# Air_Purification_System.net
KiCad netlist of a schematic drawn in Altium Designer
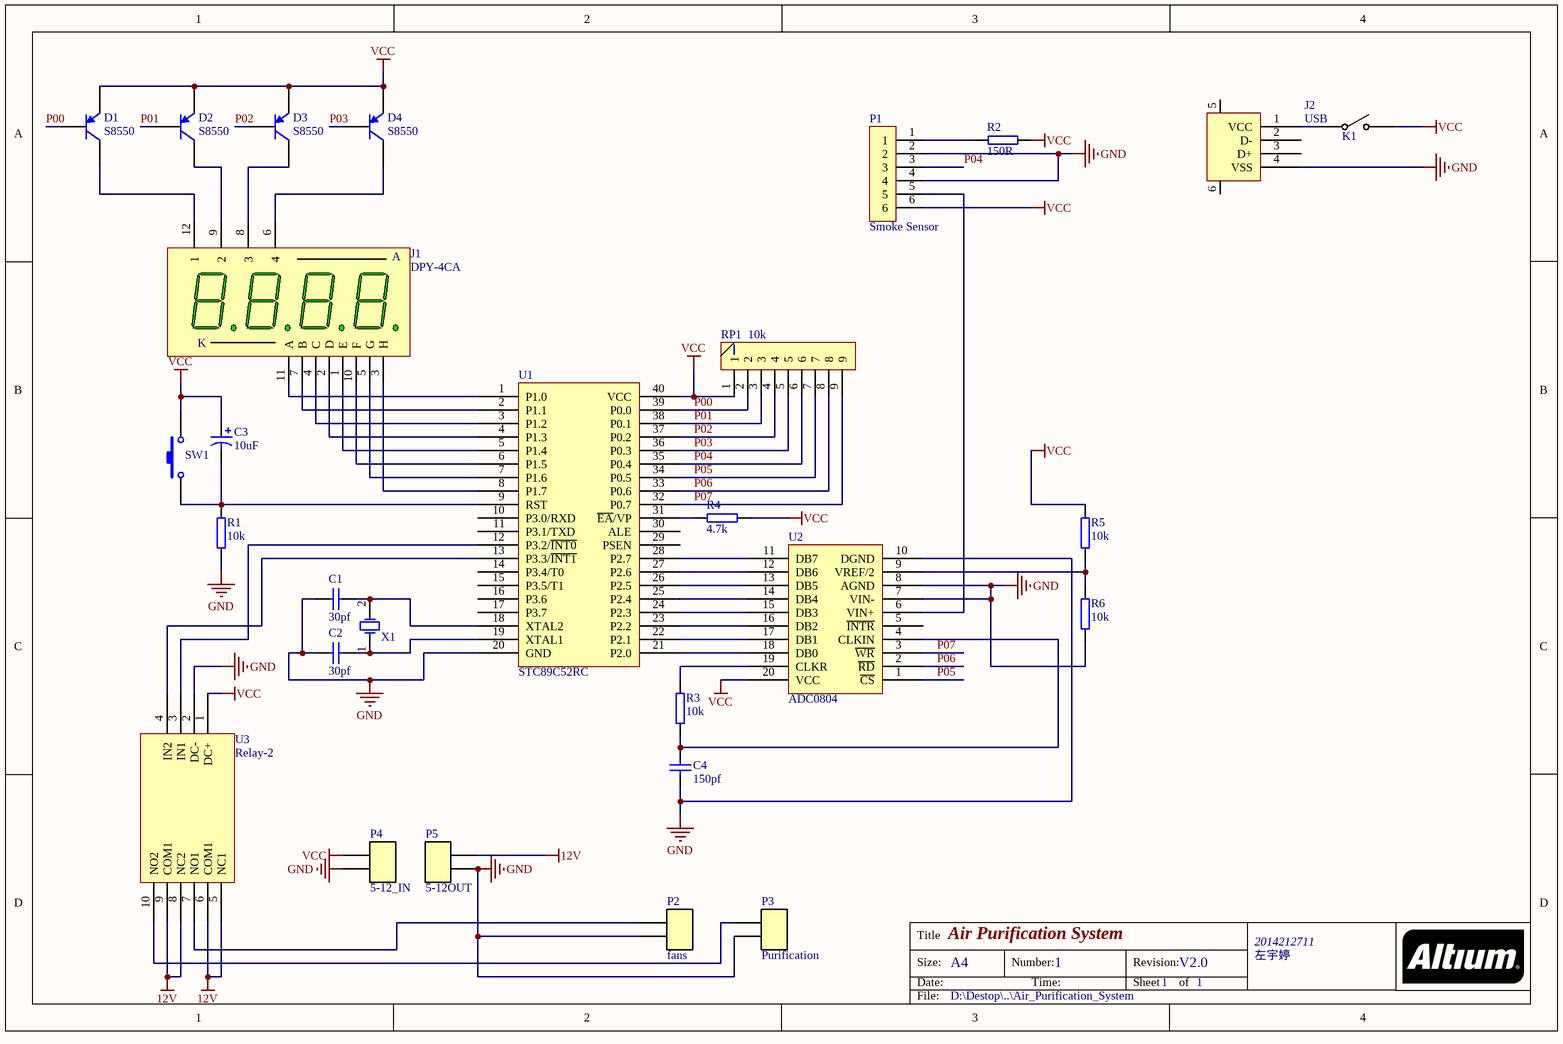
[diagram p0: Air_Purification_System.SchDoc]

(export (version "E")
  (design (tool "Eeschema 10.0.6"))
  (components
    (comp (ref "C1")
      (value "Cap")
      (footprint "cap:42:250")
      (fields (field (name "ALTIUM_UNNAMED_1") "30pf"))
      (libsource (lib "MyLib") (part "Cap"))
    )
    (comp (ref "C2")
      (value "Cap")
      (footprint "cap:42:250")
      (fields (field (name "ALTIUM_UNNAMED_1") "30pf"))
      (libsource (lib "MyLib") (part "Cap"))
    )
    (comp (ref "C3")
      (value "10uF")
      (footprint "CAP:POL:42,100")
      (fields (field (name "Comment") "Cap Pol"))
      (libsource (lib "MyLib") (part "Cap Pol"))
    )
    (comp (ref "C4")
      (value "Cap")
      (footprint "cap:42:250")
      (fields (field (name "ALTIUM_UNNAMED_1") "150pf"))
      (libsource (lib "MyLib") (part "Cap"))
    )
    (comp (ref "D1") (value "S8550") (footprint "S8550") (libsource (lib "MyLib") (part "S8550")))
    (comp (ref "D2") (value "S8550") (footprint "S8550") (libsource (lib "MyLib") (part "S8550")))
    (comp (ref "D3") (value "S8550") (footprint "S8550") (libsource (lib "MyLib") (part "S8550")))
    (comp (ref "D4") (value "S8550") (footprint "S8550") (libsource (lib "MyLib") (part "S8550")))
    (comp (ref "J1")
      (value "DPY-4CA")
      (footprint "DYP-4BIT")
      (description "共阳4位数码管")
      (libsource (lib "Fszhang") (part "DPY-4CA"))
    )
    (comp (ref "J2")
      (value "USB")
      (footprint "USB_A1")
      (description "USB接口")
      (libsource (lib "Fszhang") (part "USB"))
    )
    (comp (ref "K1")
      (value "SW")
      (footprint "SWITCH DPDT")
      (description "六角开关")
      (libsource (lib "Component") (part "SW"))
    )
    (comp (ref "P1") (value "Smoke Sensor") (footprint "6P X1") (libsource (lib "MyLib") (part "6P X1")))
    (comp (ref "P2")
      (value "fans")
      (footprint "HDR2.54-1X2")
      (description "接插件")
      (libsource (lib "Component") (part "Pin 2"))
    )
    (comp (ref "P3")
      (value "Purification")
      (footprint "HDR2.54-1X2")
      (description "接插件")
      (libsource (lib "Component") (part "Pin 2"))
    )
    (comp (ref "P4")
      (value "5-12_IN")
      (footprint "HDR2.54-1X2")
      (description "接插件")
      (libsource (lib "Component") (part "Pin 2"))
    )
    (comp (ref "P5")
      (value "5-12OUT")
      (footprint "HDR2.54-1X2")
      (description "接插件")
      (libsource (lib "") (part "Pin 2_1"))
    )
    (comp (ref "R1")
      (value "Res")
      (footprint "电阻mil:42:380")
      (fields (field (name "ALTIUM_UNNAMED_1") "10k"))
      (libsource (lib "MyLib") (part "Res"))
    )
    (comp (ref "R2")
      (value "Res")
      (footprint "电阻mil:42:380")
      (fields (field (name "ALTIUM_UNNAMED_1") "150R"))
      (libsource (lib "MyLib") (part "Res"))
    )
    (comp (ref "R3")
      (value "Res")
      (footprint "电阻mil:42:380")
      (fields (field (name "ALTIUM_UNNAMED_1") "10k"))
      (libsource (lib "MyLib") (part "Res"))
    )
    (comp (ref "R4")
      (value "Res")
      (footprint "电阻mil:42:380")
      (fields (field (name "ALTIUM_UNNAMED_1") "4.7k"))
      (libsource (lib "MyLib") (part "Res"))
    )
    (comp (ref "R5")
      (value "Res")
      (footprint "电阻mil:42:380")
      (fields (field (name "ALTIUM_UNNAMED_1") "10k"))
      (libsource (lib "MyLib") (part "Res"))
    )
    (comp (ref "R6")
      (value "Res")
      (footprint "电阻mil:42:380")
      (fields (field (name "ALTIUM_UNNAMED_1") "10k"))
      (libsource (lib "MyLib") (part "Res"))
    )
    (comp (ref "RP1")
      (value "排阻")
      (footprint "排阻")
      (fields (field (name "ALTIUM_UNNAMED_1") "10k"))
      (libsource (lib "MyLib") (part "排阻"))
    )
    (comp (ref "SW1") (value "四脚按键") (footprint "四脚按键mil:42:210:300") (libsource (lib "MyLib") (part "四脚按键")))
    (comp (ref "U1")
      (value "STC89C52RC")
      (footprint "DIP-40-2")
      (description "MCU")
      (libsource (lib "Device") (part "STC89C52RC"))
    )
    (comp (ref "U2")
      (value "ADC0804")
      (footprint "DIP-20")
      (description "ADC")
      (libsource (lib "Device") (part "ADC0804"))
    )
    (comp (ref "U3")
      (value "Relay-2")
      (footprint "PCBComponent_1")
      (libsource (lib "Relay-2") (part "Component_1"))
    )
    (comp (ref "X1") (value "晶振") (footprint "晶振") (libsource (lib "MyLib") (part "晶振")))
  )
  (nets
    (net (code "1") (name "/P00") (class "Default")
      (node (ref "D1") (pin "2") (pinfunction "B_2") (pintype "passive"))
      (node (ref "RP1") (pin "2") (pinfunction "2_2") (pintype "passive"))
      (node (ref "U1") (pin "39") (pinfunction "P0.0_39") (pintype "passive"))
    )
    (net (code "2") (name "/P01") (class "Default")
      (node (ref "D2") (pin "2") (pinfunction "B_2") (pintype "passive"))
      (node (ref "RP1") (pin "3") (pinfunction "3_3") (pintype "passive"))
      (node (ref "U1") (pin "38") (pinfunction "P0.1_38") (pintype "passive"))
    )
    (net (code "3") (name "/P02") (class "Default")
      (node (ref "D3") (pin "2") (pinfunction "B_2") (pintype "passive"))
      (node (ref "RP1") (pin "4") (pinfunction "4_4") (pintype "passive"))
      (node (ref "U1") (pin "37") (pinfunction "P0.2_37") (pintype "passive"))
    )
    (net (code "4") (name "/P03") (class "Default")
      (node (ref "D4") (pin "2") (pinfunction "B_2") (pintype "passive"))
      (node (ref "RP1") (pin "5") (pinfunction "5_5") (pintype "passive"))
      (node (ref "U1") (pin "36") (pinfunction "P0.3_36") (pintype "passive"))
    )
    (net (code "5") (name "/P04") (class "Default")
      (node (ref "P1") (pin "3") (pinfunction "3_3") (pintype "passive"))
      (node (ref "RP1") (pin "6") (pinfunction "6_6") (pintype "passive"))
      (node (ref "U1") (pin "35") (pinfunction "P0.4_35") (pintype "passive"))
    )
    (net (code "6") (name "/P05") (class "Default")
      (node (ref "RP1") (pin "7") (pinfunction "7_7") (pintype "passive"))
      (node (ref "U1") (pin "34") (pinfunction "P0.5_34") (pintype "passive"))
      (node (ref "U2") (pin "1") (pinfunction "~{CS}_1") (pintype "passive"))
    )
    (net (code "7") (name "/P06") (class "Default")
      (node (ref "RP1") (pin "8") (pinfunction "8_8") (pintype "passive"))
      (node (ref "U1") (pin "33") (pinfunction "P0.6_33") (pintype "passive"))
      (node (ref "U2") (pin "2") (pinfunction "~{RD}_2") (pintype "passive"))
    )
    (net (code "8") (name "/P07") (class "Default")
      (node (ref "RP1") (pin "9") (pinfunction "9_9") (pintype "passive"))
      (node (ref "U1") (pin "32") (pinfunction "P0.7_32") (pintype "passive"))
      (node (ref "U2") (pin "3") (pinfunction "~{WR}_3") (pintype "passive"))
    )
    (net (code "9") (name "12V") (class "Default")
      (node (ref "P5") (pin "2") (pinfunction "2_2") (pintype "passive"))
      (node (ref "U3") (pin "5") (pinfunction "NC1_5") (pintype "passive"))
      (node (ref "U3") (pin "6") (pinfunction "COM1_6") (pintype "passive"))
      (node (ref "U3") (pin "8") (pinfunction "NC2_8") (pintype "passive"))
      (node (ref "U3") (pin "9") (pinfunction "COM1_9") (pintype "passive"))
    )
    (net (code "10") (name "GND") (class "Default")
      (node (ref "C1") (pin "1") (pinfunction "1_1") (pintype "passive"))
      (node (ref "C2") (pin "1") (pinfunction "1_1") (pintype "passive"))
      (node (ref "C4") (pin "1") (pinfunction "1_1") (pintype "passive"))
      (node (ref "J2") (pin "4") (pinfunction "VSS_4") (pintype "passive"))
      (node (ref "P1") (pin "2") (pinfunction "2_2") (pintype "passive"))
      (node (ref "P1") (pin "4") (pinfunction "4_4") (pintype "passive"))
      (node (ref "P2") (pin "2") (pinfunction "2_2") (pintype "passive"))
      (node (ref "P3") (pin "2") (pinfunction "2_2") (pintype "passive"))
      (node (ref "P4") (pin "2") (pinfunction "2_2") (pintype "passive"))
      (node (ref "P5") (pin "1") (pinfunction "1_1") (pintype "passive"))
      (node (ref "R1") (pin "2") (pinfunction "2_2") (pintype "passive"))
      (node (ref "R6") (pin "1") (pinfunction "1_1") (pintype "passive"))
      (node (ref "U1") (pin "20") (pinfunction "GND_20") (pintype "passive"))
      (node (ref "U2") (pin "10") (pinfunction "DGND_10") (pintype "passive"))
      (node (ref "U2") (pin "7") (pinfunction "VIN-_7") (pintype "passive"))
      (node (ref "U2") (pin "8") (pinfunction "AGND_8") (pintype "passive"))
      (node (ref "U3") (pin "2") (pinfunction "DC-_2") (pintype "passive"))
    )
    (net (code "11") (name "Net-(D1-C)") (class "Default")
      (node (ref "D1") (pin "3") (pinfunction "C_3") (pintype "passive"))
      (node (ref "J1") (pin "12") (pinfunction "1_12") (pintype "passive"))
    )
    (net (code "12") (name "Net-(D2-C)") (class "Default")
      (node (ref "D2") (pin "3") (pinfunction "C_3") (pintype "passive"))
      (node (ref "J1") (pin "9") (pinfunction "2_9") (pintype "passive"))
    )
    (net (code "13") (name "Net-(D3-C)") (class "Default")
      (node (ref "D3") (pin "3") (pinfunction "C_3") (pintype "passive"))
      (node (ref "J1") (pin "8") (pinfunction "3_8") (pintype "passive"))
    )
    (net (code "14") (name "Net-(D4-C)") (class "Default")
      (node (ref "D4") (pin "3") (pinfunction "C_3") (pintype "passive"))
      (node (ref "J1") (pin "6") (pinfunction "4_6") (pintype "passive"))
    )
    (net (code "15") (name "Net-(J1-A)") (class "Default")
      (node (ref "J1") (pin "11") (pinfunction "A_11") (pintype "passive"))
      (node (ref "U1") (pin "1") (pinfunction "P1.0_1") (pintype "passive"))
    )
    (net (code "16") (name "Net-(J1-B)") (class "Default")
      (node (ref "J1") (pin "7") (pinfunction "B_7") (pintype "passive"))
      (node (ref "U1") (pin "2") (pinfunction "P1.1_2") (pintype "passive"))
    )
    (net (code "17") (name "Net-(J1-C)") (class "Default")
      (node (ref "J1") (pin "4") (pinfunction "C_4") (pintype "passive"))
      (node (ref "U1") (pin "3") (pinfunction "P1.2_3") (pintype "passive"))
    )
    (net (code "18") (name "Net-(J1-D)") (class "Default")
      (node (ref "J1") (pin "2") (pinfunction "D_2") (pintype "passive"))
      (node (ref "U1") (pin "4") (pinfunction "P1.3_4") (pintype "passive"))
    )
    (net (code "19") (name "Net-(J1-E)") (class "Default")
      (node (ref "J1") (pin "1") (pinfunction "E_1") (pintype "passive"))
      (node (ref "U1") (pin "5") (pinfunction "P1.4_5") (pintype "passive"))
    )
    (net (code "20") (name "Net-(J1-F)") (class "Default")
      (node (ref "J1") (pin "10") (pinfunction "F_10") (pintype "passive"))
      (node (ref "U1") (pin "6") (pinfunction "P1.5_6") (pintype "passive"))
    )
    (net (code "21") (name "Net-(J1-G)") (class "Default")
      (node (ref "J1") (pin "5") (pinfunction "G_5") (pintype "passive"))
      (node (ref "U1") (pin "7") (pinfunction "P1.6_7") (pintype "passive"))
    )
    (net (code "22") (name "Net-(J1-H)") (class "Default")
      (node (ref "J1") (pin "3") (pinfunction "H_3") (pintype "passive"))
      (node (ref "U1") (pin "8") (pinfunction "P1.7_8") (pintype "passive"))
    )
    (net (code "23") (name "Net-(J2-VCC)") (class "Default")
      (node (ref "J2") (pin "1") (pinfunction "VCC_1") (pintype "passive"))
      (node (ref "K1") (pin "2") (pinfunction "COMMON_2") (pintype "passive"))
    )
    (net (code "24") (name "Net-(P1-Pad1)") (class "Default")
      (node (ref "P1") (pin "1") (pinfunction "1_1") (pintype "passive"))
      (node (ref "R2") (pin "1") (pinfunction "1_1") (pintype "passive"))
    )
    (net (code "25") (name "Net-(U1-P2.0)") (class "Default")
      (node (ref "U1") (pin "21") (pinfunction "P2.0_21") (pintype "passive"))
      (node (ref "U2") (pin "18") (pinfunction "DB0_18") (pintype "passive"))
    )
    (net (code "26") (name "Net-(U1-P2.1)") (class "Default")
      (node (ref "U1") (pin "22") (pinfunction "P2.1_22") (pintype "passive"))
      (node (ref "U2") (pin "17") (pinfunction "DB1_17") (pintype "passive"))
    )
    (net (code "27") (name "Net-(U1-P2.2)") (class "Default")
      (node (ref "U1") (pin "23") (pinfunction "P2.2_23") (pintype "passive"))
      (node (ref "U2") (pin "16") (pinfunction "DB2_16") (pintype "passive"))
    )
    (net (code "28") (name "Net-(U1-P2.3)") (class "Default")
      (node (ref "U1") (pin "24") (pinfunction "P2.3_24") (pintype "passive"))
      (node (ref "U2") (pin "15") (pinfunction "DB3_15") (pintype "passive"))
    )
    (net (code "29") (name "Net-(U1-P2.4)") (class "Default")
      (node (ref "U1") (pin "25") (pinfunction "P2.4_25") (pintype "passive"))
      (node (ref "U2") (pin "14") (pinfunction "DB4_14") (pintype "passive"))
    )
    (net (code "30") (name "Net-(U1-P2.5)") (class "Default")
      (node (ref "U1") (pin "26") (pinfunction "P2.5_26") (pintype "passive"))
      (node (ref "U2") (pin "13") (pinfunction "DB5_13") (pintype "passive"))
    )
    (net (code "31") (name "Net-(U1-P2.6)") (class "Default")
      (node (ref "U1") (pin "27") (pinfunction "P2.6_27") (pintype "passive"))
      (node (ref "U2") (pin "12") (pinfunction "DB6_12") (pintype "passive"))
    )
    (net (code "32") (name "Net-(U1-P2.7)") (class "Default")
      (node (ref "U1") (pin "28") (pinfunction "P2.7_28") (pintype "passive"))
      (node (ref "U2") (pin "11") (pinfunction "DB7_11") (pintype "passive"))
    )
    (net (code "33") (name "Net-(U1-P3.2{slash}~{INT0})") (class "Default")
      (node (ref "U1") (pin "12") (pinfunction "P3.2/~{INT0}_12") (pintype "passive"))
      (node (ref "U3") (pin "3") (pinfunction "IN1_3") (pintype "passive"))
    )
    (net (code "34") (name "Net-(U1-P3.3{slash}~{INT1})") (class "Default")
      (node (ref "U1") (pin "13") (pinfunction "P3.3/~{INT1}_13") (pintype "passive"))
      (node (ref "U3") (pin "4") (pinfunction "IN2_4") (pintype "passive"))
    )
    (net (code "35") (name "Net-(U1-RST)") (class "Default")
      (node (ref "C3") (pin "2") (pinfunction "2_2") (pintype "passive"))
      (node (ref "R1") (pin "1") (pinfunction "1_1") (pintype "passive"))
      (node (ref "SW1") (pin "1") (pinfunction "1_1") (pintype "passive"))
      (node (ref "U1") (pin "9") (pinfunction "RST_9") (pintype "passive"))
    )
    (net (code "36") (name "Net-(U1-XTAL1)") (class "Default")
      (node (ref "C2") (pin "2") (pinfunction "2_2") (pintype "passive"))
      (node (ref "U1") (pin "19") (pinfunction "XTAL1_19") (pintype "passive"))
      (node (ref "X1") (pin "1") (pinfunction "OSC1_1") (pintype "passive"))
    )
    (net (code "37") (name "Net-(U1-XTAL2)") (class "Default")
      (node (ref "C1") (pin "2") (pinfunction "2_2") (pintype "passive"))
      (node (ref "U1") (pin "18") (pinfunction "XTAL2_18") (pintype "passive"))
      (node (ref "X1") (pin "2") (pinfunction "OSC2_2") (pintype "passive"))
    )
    (net (code "38") (name "Net-(U1-~{EA}{slash}VP)") (class "Default")
      (node (ref "R4") (pin "2") (pinfunction "2_2") (pintype "passive"))
      (node (ref "U1") (pin "31") (pinfunction "~{EA}/VP_31") (pintype "passive"))
    )
    (net (code "39") (name "Net-(U2-CLKIN)") (class "Default")
      (node (ref "C4") (pin "2") (pinfunction "2_2") (pintype "passive"))
      (node (ref "R3") (pin "1") (pinfunction "1_1") (pintype "passive"))
      (node (ref "U2") (pin "4") (pinfunction "CLKIN_4") (pintype "passive"))
    )
    (net (code "40") (name "Net-(U2-CLKR)") (class "Default")
      (node (ref "R3") (pin "2") (pinfunction "2_2") (pintype "passive"))
      (node (ref "U2") (pin "19") (pinfunction "CLKR_19") (pintype "passive"))
    )
    (net (code "41") (name "Net-(U2-VIN+)") (class "Default")
      (node (ref "P1") (pin "5") (pinfunction "5_5") (pintype "passive"))
      (node (ref "U2") (pin "6") (pinfunction "VIN+_6") (pintype "passive"))
    )
    (net (code "42") (name "Net-(U2-VREF{slash}2)") (class "Default")
      (node (ref "R5") (pin "1") (pinfunction "1_1") (pintype "passive"))
      (node (ref "R6") (pin "2") (pinfunction "2_2") (pintype "passive"))
      (node (ref "U2") (pin "9") (pinfunction "VREF/2_9") (pintype "passive"))
    )
    (net (code "43") (name "Net-(U3-NO1)") (class "Default")
      (node (ref "P2") (pin "1") (pinfunction "1_1") (pintype "passive"))
      (node (ref "U3") (pin "7") (pinfunction "NO1_7") (pintype "passive"))
    )
    (net (code "44") (name "Net-(U3-NO2)") (class "Default")
      (node (ref "P3") (pin "1") (pinfunction "1_1") (pintype "passive"))
      (node (ref "U3") (pin "10") (pinfunction "NO2_10") (pintype "passive"))
    )
    (net (code "45") (name "VCC") (class "Default")
      (node (ref "C3") (pin "1") (pinfunction "1_1") (pintype "passive"))
      (node (ref "D1") (pin "1") (pinfunction "E_1") (pintype "passive"))
      (node (ref "D2") (pin "1") (pinfunction "E_1") (pintype "passive"))
      (node (ref "D3") (pin "1") (pinfunction "E_1") (pintype "passive"))
      (node (ref "D4") (pin "1") (pinfunction "E_1") (pintype "passive"))
      (node (ref "K1") (pin "1") (pinfunction "NO_1") (pintype "passive"))
      (node (ref "P1") (pin "6") (pinfunction "6_6") (pintype "passive"))
      (node (ref "P4") (pin "1") (pinfunction "1_1") (pintype "passive"))
      (node (ref "R2") (pin "2") (pinfunction "2_2") (pintype "passive"))
      (node (ref "R4") (pin "1") (pinfunction "1_1") (pintype "passive"))
      (node (ref "R5") (pin "2") (pinfunction "2_2") (pintype "passive"))
      (node (ref "RP1") (pin "1") (pinfunction "1_1") (pintype "passive"))
      (node (ref "SW1") (pin "4") (pinfunction "4_4") (pintype "passive"))
      (node (ref "U1") (pin "40") (pinfunction "VCC_40") (pintype "passive"))
      (node (ref "U2") (pin "20") (pinfunction "VCC_20") (pintype "passive"))
      (node (ref "U3") (pin "1") (pinfunction "DC+_1") (pintype "passive"))
    )
    (net (code "46") (name "unconnected-(J2-D+-Pad3)") (class "Default")
      (node (ref "J2") (pin "3") (pinfunction "D+_3") (pintype "passive"))
    )
    (net (code "47") (name "unconnected-(J2-D--Pad2)") (class "Default")
      (node (ref "J2") (pin "2") (pinfunction "D-_2") (pintype "passive"))
    )
    (net (code "48") (name "unconnected-(J2-Pad5)") (class "Default")
      (node (ref "J2") (pin "5") (pinfunction "5_5") (pintype "passive"))
    )
    (net (code "49") (name "unconnected-(J2-Pad6)") (class "Default")
      (node (ref "J2") (pin "6") (pinfunction "6_6") (pintype "passive"))
    )
    (net (code "50") (name "unconnected-(SW1-Pad2)") (class "Default")
      (node (ref "SW1") (pin "2") (pinfunction "2_2") (pintype "passive"))
    )
    (net (code "51") (name "unconnected-(SW1-Pad3)") (class "Default")
      (node (ref "SW1") (pin "3") (pinfunction "3_3") (pintype "passive"))
    )
    (net (code "52") (name "unconnected-(U1-ALE-Pad30)") (class "Default")
      (node (ref "U1") (pin "30") (pinfunction "ALE_30") (pintype "passive"))
    )
    (net (code "53") (name "unconnected-(U1-P3.0{slash}RXD-Pad10)") (class "Default")
      (node (ref "U1") (pin "10") (pinfunction "P3.0/RXD_10") (pintype "passive"))
    )
    (net (code "54") (name "unconnected-(U1-P3.1{slash}TXD-Pad11)") (class "Default")
      (node (ref "U1") (pin "11") (pinfunction "P3.1/TXD_11") (pintype "passive"))
    )
    (net (code "55") (name "unconnected-(U1-P3.4{slash}T0-Pad14)") (class "Default")
      (node (ref "U1") (pin "14") (pinfunction "P3.4/T0_14") (pintype "passive"))
    )
    (net (code "56") (name "unconnected-(U1-P3.5{slash}T1-Pad15)") (class "Default")
      (node (ref "U1") (pin "15") (pinfunction "P3.5/T1_15") (pintype "passive"))
    )
    (net (code "57") (name "unconnected-(U1-P3.6-Pad16)") (class "Default")
      (node (ref "U1") (pin "16") (pinfunction "P3.6_16") (pintype "passive"))
    )
    (net (code "58") (name "unconnected-(U1-P3.7-Pad17)") (class "Default")
      (node (ref "U1") (pin "17") (pinfunction "P3.7_17") (pintype "passive"))
    )
    (net (code "59") (name "unconnected-(U1-PSEN-Pad29)") (class "Default")
      (node (ref "U1") (pin "29") (pinfunction "PSEN_29") (pintype "passive"))
    )
    (net (code "60") (name "unconnected-(U2-~{INTR}-Pad5)") (class "Default")
      (node (ref "U2") (pin "5") (pinfunction "~{INTR}_5") (pintype "passive"))
    )
  )
)
